# RegisterA.net
KiCad netlist of a schematic drawn in Altium Designer
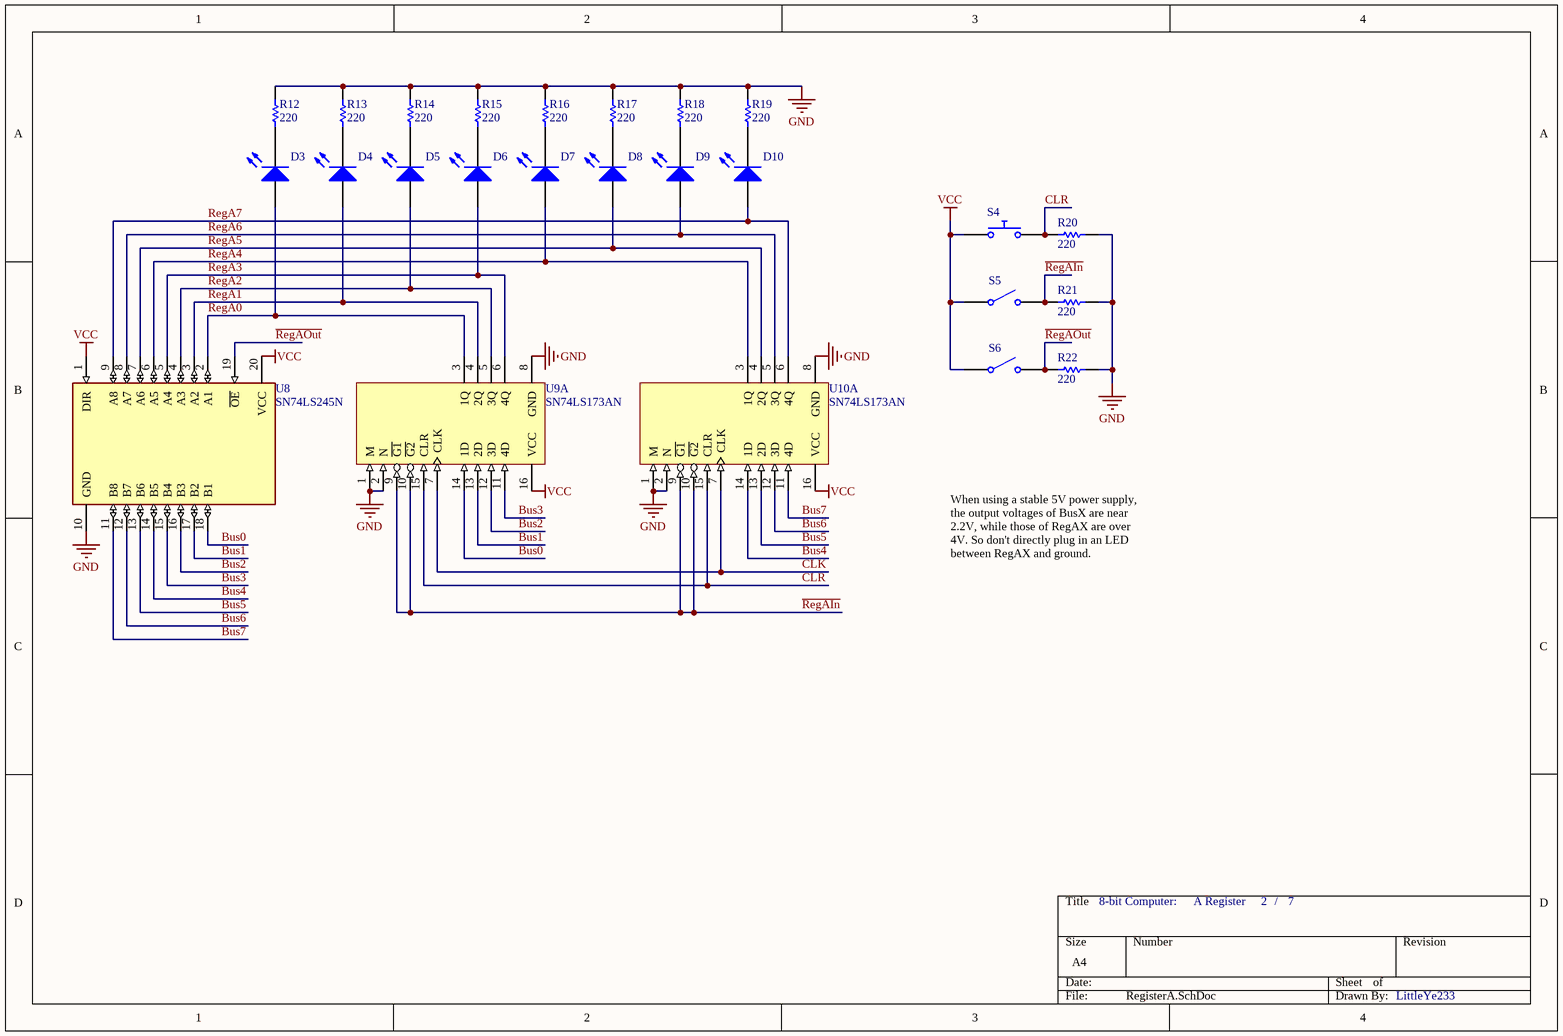
[diagram p0: RegisterA.SchDoc]

(export (version "E")
  (design (tool "Eeschema 10.0.6"))
  (components
    (comp (ref "D3")
      (value "Light-Emitting Diode")
      (libsource (lib "Simulation Generic Components") (part "LED"))
    )
    (comp (ref "D4")
      (value "Light-Emitting Diode")
      (libsource (lib "Simulation Generic Components") (part "LED"))
    )
    (comp (ref "D5")
      (value "Light-Emitting Diode")
      (libsource (lib "Simulation Generic Components") (part "LED"))
    )
    (comp (ref "D6")
      (value "Light-Emitting Diode")
      (libsource (lib "Simulation Generic Components") (part "LED"))
    )
    (comp (ref "D7")
      (value "Light-Emitting Diode")
      (libsource (lib "Simulation Generic Components") (part "LED"))
    )
    (comp (ref "D8")
      (value "Light-Emitting Diode")
      (libsource (lib "Simulation Generic Components") (part "LED"))
    )
    (comp (ref "D9")
      (value "Light-Emitting Diode")
      (libsource (lib "Simulation Generic Components") (part "LED"))
    )
    (comp (ref "D10")
      (value "Light-Emitting Diode")
      (libsource (lib "Simulation Generic Components") (part "LED"))
    )
    (comp (ref "R12")
      (value "220")
      (description "Resistor")
      (libsource (lib "Simulation Generic Components") (part "Resistor"))
    )
    (comp (ref "R13")
      (value "220")
      (description "Resistor")
      (libsource (lib "Simulation Generic Components") (part "Resistor"))
    )
    (comp (ref "R14")
      (value "220")
      (description "Resistor")
      (libsource (lib "Simulation Generic Components") (part "Resistor"))
    )
    (comp (ref "R15")
      (value "220")
      (description "Resistor")
      (libsource (lib "Simulation Generic Components") (part "Resistor"))
    )
    (comp (ref "R16")
      (value "220")
      (description "Resistor")
      (libsource (lib "Simulation Generic Components") (part "Resistor"))
    )
    (comp (ref "R17")
      (value "220")
      (description "Resistor")
      (libsource (lib "Simulation Generic Components") (part "Resistor"))
    )
    (comp (ref "R18")
      (value "220")
      (description "Resistor")
      (libsource (lib "Simulation Generic Components") (part "Resistor"))
    )
    (comp (ref "R19")
      (value "220")
      (description "Resistor")
      (libsource (lib "Simulation Generic Components") (part "Resistor"))
    )
    (comp (ref "R20")
      (value "220")
      (description "Resistor")
      (libsource (lib "Simulation Generic Components") (part "Resistor"))
    )
    (comp (ref "R21")
      (value "220")
      (description "Resistor")
      (libsource (lib "Simulation Generic Components") (part "Resistor"))
    )
    (comp (ref "R22")
      (value "220")
      (description "Resistor")
      (libsource (lib "Simulation Generic Components") (part "Resistor"))
    )
    (comp (ref "S4")
      (value "Push Button Normally Opened")
      (libsource (lib "Simulation Generic Components") (part "Push Button NO"))
    )
    (comp (ref "S5")
      (value "Single-Pole, Single-Throw Switch")
      (libsource (lib "Simulation Generic Components") (part "SPST SW"))
    )
    (comp (ref "S6")
      (value "Single-Pole, Single-Throw Switch")
      (libsource (lib "Simulation Generic Components") (part "SPST SW"))
    )
    (comp (ref "U8")
      (value "SN74LS245N")
      (footprint "FP-N0020A-MFG")
      (description "IC TXRX NON-INVERT 5.25V 20DIP")
      (libsource (lib "SN74LS245N") (part "CMP-1620-00419-3"))
    )
    (comp (ref "U9")
      (value "SN74LS173AN")
      (footprint "N0016A")
      (description "4-Bit D-type Registers with 3-State Outputs, N0016A, TUBE")
      (fields
        (field (name "MANUFACTURER") "Texas Instruments")
        (field (name "GENERIC PART NUMBER") "SN74LS173A")
      )
      (libsource (lib "SN74LS173AN") (part "CMP-1619-00777-2"))
    )
    (comp (ref "U10")
      (value "SN74LS173AN")
      (footprint "N0016A")
      (description "4-Bit D-type Registers with 3-State Outputs, N0016A, TUBE")
      (fields
        (field (name "MANUFACTURER") "Texas Instruments")
        (field (name "GENERIC PART NUMBER") "SN74LS173A")
      )
      (libsource (lib "SN74LS173AN") (part "CMP-1619-00777-2"))
    )
  )
  (nets
    (net (code "1") (name "/Bus0") (class "Default")
      (node (ref "U8") (pin "18") (pinfunction "B1_18") (pintype "bidirectional"))
      (node (ref "U9") (pin "14") (pinfunction "1D_14") (pintype "input"))
    )
    (net (code "2") (name "/Bus1") (class "Default")
      (node (ref "U8") (pin "17") (pinfunction "B2_17") (pintype "bidirectional"))
      (node (ref "U9") (pin "13") (pinfunction "2D_13") (pintype "input"))
    )
    (net (code "3") (name "/Bus2") (class "Default")
      (node (ref "U8") (pin "16") (pinfunction "B3_16") (pintype "bidirectional"))
      (node (ref "U9") (pin "12") (pinfunction "3D_12") (pintype "input"))
    )
    (net (code "4") (name "/Bus3") (class "Default")
      (node (ref "U8") (pin "15") (pinfunction "B4_15") (pintype "bidirectional"))
      (node (ref "U9") (pin "11") (pinfunction "4D_11") (pintype "input"))
    )
    (net (code "5") (name "/Bus4") (class "Default")
      (node (ref "U10") (pin "14") (pinfunction "1D_14") (pintype "input"))
      (node (ref "U8") (pin "14") (pinfunction "B5_14") (pintype "bidirectional"))
    )
    (net (code "6") (name "/Bus5") (class "Default")
      (node (ref "U10") (pin "13") (pinfunction "2D_13") (pintype "input"))
      (node (ref "U8") (pin "13") (pinfunction "B6_13") (pintype "bidirectional"))
    )
    (net (code "7") (name "/Bus6") (class "Default")
      (node (ref "U10") (pin "12") (pinfunction "3D_12") (pintype "input"))
      (node (ref "U8") (pin "12") (pinfunction "B7_12") (pintype "bidirectional"))
    )
    (net (code "8") (name "/Bus7") (class "Default")
      (node (ref "U10") (pin "11") (pinfunction "4D_11") (pintype "input"))
      (node (ref "U8") (pin "11") (pinfunction "B8_11") (pintype "bidirectional"))
    )
    (net (code "9") (name "/CLK") (class "Default")
      (node (ref "U10") (pin "7") (pinfunction "CLK_7") (pintype "input"))
      (node (ref "U9") (pin "7") (pinfunction "CLK_7") (pintype "input"))
    )
    (net (code "10") (name "/CLR") (class "Default")
      (node (ref "R20") (pin "2") (pinfunction "2_2") (pintype "passive"))
      (node (ref "S4") (pin "2") (pinfunction "2_2") (pintype "passive"))
      (node (ref "U10") (pin "15") (pinfunction "CLR_15") (pintype "input"))
      (node (ref "U9") (pin "15") (pinfunction "CLR_15") (pintype "input"))
    )
    (net (code "11") (name "/RegA0") (class "Default")
      (node (ref "D3") (pin "1") (pinfunction "A_1") (pintype "passive"))
      (node (ref "U8") (pin "2") (pinfunction "A1_2") (pintype "bidirectional"))
      (node (ref "U9") (pin "3") (pinfunction "1Q_3") (pintype "tri_state"))
    )
    (net (code "12") (name "/RegA1") (class "Default")
      (node (ref "D4") (pin "1") (pinfunction "A_1") (pintype "passive"))
      (node (ref "U8") (pin "3") (pinfunction "A2_3") (pintype "bidirectional"))
      (node (ref "U9") (pin "4") (pinfunction "2Q_4") (pintype "tri_state"))
    )
    (net (code "13") (name "/RegA2") (class "Default")
      (node (ref "D5") (pin "1") (pinfunction "A_1") (pintype "passive"))
      (node (ref "U8") (pin "4") (pinfunction "A3_4") (pintype "bidirectional"))
      (node (ref "U9") (pin "5") (pinfunction "3Q_5") (pintype "tri_state"))
    )
    (net (code "14") (name "/RegA3") (class "Default")
      (node (ref "D6") (pin "1") (pinfunction "A_1") (pintype "passive"))
      (node (ref "U8") (pin "5") (pinfunction "A4_5") (pintype "bidirectional"))
      (node (ref "U9") (pin "6") (pinfunction "4Q_6") (pintype "tri_state"))
    )
    (net (code "15") (name "/RegA4") (class "Default")
      (node (ref "D7") (pin "1") (pinfunction "A_1") (pintype "passive"))
      (node (ref "U10") (pin "3") (pinfunction "1Q_3") (pintype "tri_state"))
      (node (ref "U8") (pin "6") (pinfunction "A5_6") (pintype "bidirectional"))
    )
    (net (code "16") (name "/RegA5") (class "Default")
      (node (ref "D8") (pin "1") (pinfunction "A_1") (pintype "passive"))
      (node (ref "U10") (pin "4") (pinfunction "2Q_4") (pintype "tri_state"))
      (node (ref "U8") (pin "7") (pinfunction "A6_7") (pintype "bidirectional"))
    )
    (net (code "17") (name "/RegA6") (class "Default")
      (node (ref "D9") (pin "1") (pinfunction "A_1") (pintype "passive"))
      (node (ref "U10") (pin "5") (pinfunction "3Q_5") (pintype "tri_state"))
      (node (ref "U8") (pin "8") (pinfunction "A7_8") (pintype "bidirectional"))
    )
    (net (code "18") (name "/RegA7") (class "Default")
      (node (ref "D10") (pin "1") (pinfunction "A_1") (pintype "passive"))
      (node (ref "U10") (pin "6") (pinfunction "4Q_6") (pintype "tri_state"))
      (node (ref "U8") (pin "9") (pinfunction "A8_9") (pintype "bidirectional"))
    )
    (net (code "19") (name "/~{RegAIn}") (class "Default")
      (node (ref "R21") (pin "2") (pinfunction "2_2") (pintype "passive"))
      (node (ref "S5") (pin "2") (pinfunction "2_2") (pintype "passive"))
      (node (ref "U10") (pin "10") (pinfunction "~{G2}_10") (pintype "input"))
      (node (ref "U10") (pin "9") (pinfunction "~{G1}_9") (pintype "input"))
      (node (ref "U9") (pin "10") (pinfunction "~{G2}_10") (pintype "input"))
      (node (ref "U9") (pin "9") (pinfunction "~{G1}_9") (pintype "input"))
    )
    (net (code "20") (name "/~{RegAOut}") (class "Default")
      (node (ref "R22") (pin "2") (pinfunction "2_2") (pintype "passive"))
      (node (ref "S6") (pin "2") (pinfunction "2_2") (pintype "passive"))
      (node (ref "U8") (pin "19") (pinfunction "~{OE}_19") (pintype "input"))
    )
    (net (code "21") (name "GND") (class "Default")
      (node (ref "R12") (pin "2") (pinfunction "2_2") (pintype "passive"))
      (node (ref "R13") (pin "2") (pinfunction "2_2") (pintype "passive"))
      (node (ref "R14") (pin "2") (pinfunction "2_2") (pintype "passive"))
      (node (ref "R15") (pin "2") (pinfunction "2_2") (pintype "passive"))
      (node (ref "R16") (pin "2") (pinfunction "2_2") (pintype "passive"))
      (node (ref "R17") (pin "2") (pinfunction "2_2") (pintype "passive"))
      (node (ref "R18") (pin "2") (pinfunction "2_2") (pintype "passive"))
      (node (ref "R19") (pin "2") (pinfunction "2_2") (pintype "passive"))
      (node (ref "R20") (pin "1") (pinfunction "1_1") (pintype "passive"))
      (node (ref "R21") (pin "1") (pinfunction "1_1") (pintype "passive"))
      (node (ref "R22") (pin "1") (pinfunction "1_1") (pintype "passive"))
      (node (ref "U10") (pin "1") (pinfunction "M_1") (pintype "input"))
      (node (ref "U10") (pin "2") (pinfunction "N_2") (pintype "input"))
      (node (ref "U10") (pin "8") (pinfunction "GND_8") (pintype "power_in"))
      (node (ref "U8") (pin "10") (pinfunction "GND_10") (pintype "power_in"))
      (node (ref "U9") (pin "1") (pinfunction "M_1") (pintype "input"))
      (node (ref "U9") (pin "2") (pinfunction "N_2") (pintype "input"))
      (node (ref "U9") (pin "8") (pinfunction "GND_8") (pintype "power_in"))
    )
    (net (code "22") (name "Net-(D3-K)") (class "Default")
      (node (ref "D3") (pin "2") (pinfunction "K_2") (pintype "passive"))
      (node (ref "R12") (pin "1") (pinfunction "1_1") (pintype "passive"))
    )
    (net (code "23") (name "Net-(D4-K)") (class "Default")
      (node (ref "D4") (pin "2") (pinfunction "K_2") (pintype "passive"))
      (node (ref "R13") (pin "1") (pinfunction "1_1") (pintype "passive"))
    )
    (net (code "24") (name "Net-(D5-K)") (class "Default")
      (node (ref "D5") (pin "2") (pinfunction "K_2") (pintype "passive"))
      (node (ref "R14") (pin "1") (pinfunction "1_1") (pintype "passive"))
    )
    (net (code "25") (name "Net-(D6-K)") (class "Default")
      (node (ref "D6") (pin "2") (pinfunction "K_2") (pintype "passive"))
      (node (ref "R15") (pin "1") (pinfunction "1_1") (pintype "passive"))
    )
    (net (code "26") (name "Net-(D7-K)") (class "Default")
      (node (ref "D7") (pin "2") (pinfunction "K_2") (pintype "passive"))
      (node (ref "R16") (pin "1") (pinfunction "1_1") (pintype "passive"))
    )
    (net (code "27") (name "Net-(D8-K)") (class "Default")
      (node (ref "D8") (pin "2") (pinfunction "K_2") (pintype "passive"))
      (node (ref "R17") (pin "1") (pinfunction "1_1") (pintype "passive"))
    )
    (net (code "28") (name "Net-(D9-K)") (class "Default")
      (node (ref "D9") (pin "2") (pinfunction "K_2") (pintype "passive"))
      (node (ref "R18") (pin "1") (pinfunction "1_1") (pintype "passive"))
    )
    (net (code "29") (name "Net-(D10-K)") (class "Default")
      (node (ref "D10") (pin "2") (pinfunction "K_2") (pintype "passive"))
      (node (ref "R19") (pin "1") (pinfunction "1_1") (pintype "passive"))
    )
    (net (code "30") (name "VCC") (class "Default")
      (node (ref "S4") (pin "1") (pinfunction "1_1") (pintype "passive"))
      (node (ref "S5") (pin "1") (pinfunction "1_1") (pintype "passive"))
      (node (ref "S6") (pin "1") (pinfunction "1_1") (pintype "passive"))
      (node (ref "U10") (pin "16") (pinfunction "VCC_16") (pintype "power_in"))
      (node (ref "U8") (pin "1") (pinfunction "DIR_1") (pintype "input"))
      (node (ref "U8") (pin "20") (pinfunction "VCC_20") (pintype "power_in"))
      (node (ref "U9") (pin "16") (pinfunction "VCC_16") (pintype "power_in"))
    )
  )
)
